# 2button_LED_series.net
KiCad netlist of a schematic drawn in EAGLE
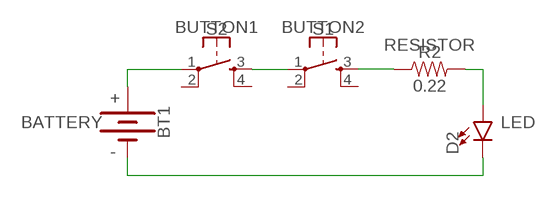
[diagram p0: schematic, sheet 1]

(export (version "E")
  (design (tool "Eeschema 10.0.6"))
  (components
    (comp (ref "BT1")
      (value "BATTERY-9V")
      (footprint "eagle-import:BATTCON_9V")
      (libsource (lib "eagle-import") (part "BATTERY-9V"))
    )
    (comp (ref "D2")
      (value "LED5MM")
      (footprint "eagle-import:LED_5MM")
      (libsource (lib "eagle-import") (part "LED5MM"))
    )
    (comp (ref "R2")
      (value "0.22")
      (footprint "eagle-import:0805")
      (libsource (lib "eagle-import") (part "0.22OHM-0805-1/4W-1%"))
    )
    (comp (ref "S1")
      (value "MOMENTARY-SWITCH-SPST-2-SMD-4.6X2.8MM")
      (footprint "eagle-import:TACTILE_SWITCH_SMD_4.6X2.8MM")
      (libsource (lib "eagle-import") (part "MOMENTARY-SWITCH-SPST-2-SMD-4.6X2.8MM"))
    )
    (comp (ref "S2")
      (value "MOMENTARY-SWITCH-SPST-2-SMD-4.6X2.8MM")
      (footprint "eagle-import:TACTILE_SWITCH_SMD_4.6X2.8MM")
      (libsource (lib "eagle-import") (part "MOMENTARY-SWITCH-SPST-2-SMD-4.6X2.8MM"))
    )
  )
  (nets
    (net (code "1") (name "Net-(BT1-Pad+)") (class "Default")
      (node (ref "BT1") (pin "+") (pinfunction "+_+") (pintype "power_in"))
      (node (ref "S2") (pin "1") (pinfunction "1_1") (pintype "passive"))
    )
    (net (code "2") (name "Net-(D2-C)") (class "Default")
      (node (ref "BT1") (pin "-") (pinfunction "-_-") (pintype "power_in"))
      (node (ref "D2") (pin "K") (pinfunction "C_K") (pintype "passive"))
    )
    (net (code "3") (name "Net-(D2-PadA)") (class "Default")
      (node (ref "D2") (pin "A") (pinfunction "A_A") (pintype "passive"))
      (node (ref "R2") (pin "2") (pinfunction "2_2") (pintype "passive"))
    )
    (net (code "4") (name "Net-(R2-Pad1)") (class "Default")
      (node (ref "R2") (pin "1") (pinfunction "1_1") (pintype "passive"))
      (node (ref "S1") (pin "3") (pinfunction "3_3") (pintype "passive"))
    )
    (net (code "5") (name "Net-(S1-Pad1)") (class "Default")
      (node (ref "S1") (pin "1") (pinfunction "1_1") (pintype "passive"))
      (node (ref "S2") (pin "3") (pinfunction "3_3") (pintype "passive"))
    )
    (net (code "6") (name "unconnected-(S1-Pad2)") (class "Default")
      (node (ref "S1") (pin "2") (pinfunction "2_2") (pintype "passive"))
    )
    (net (code "7") (name "unconnected-(S1-Pad4)") (class "Default")
      (node (ref "S1") (pin "4") (pinfunction "4_4") (pintype "passive"))
    )
    (net (code "8") (name "unconnected-(S2-Pad2)") (class "Default")
      (node (ref "S2") (pin "2") (pinfunction "2_2") (pintype "passive"))
    )
    (net (code "9") (name "unconnected-(S2-Pad4)") (class "Default")
      (node (ref "S2") (pin "4") (pinfunction "4_4") (pintype "passive"))
    )
  )
)
